# CutMonitor_MCU.net
KiCad netlist of a schematic drawn in Altium Designer
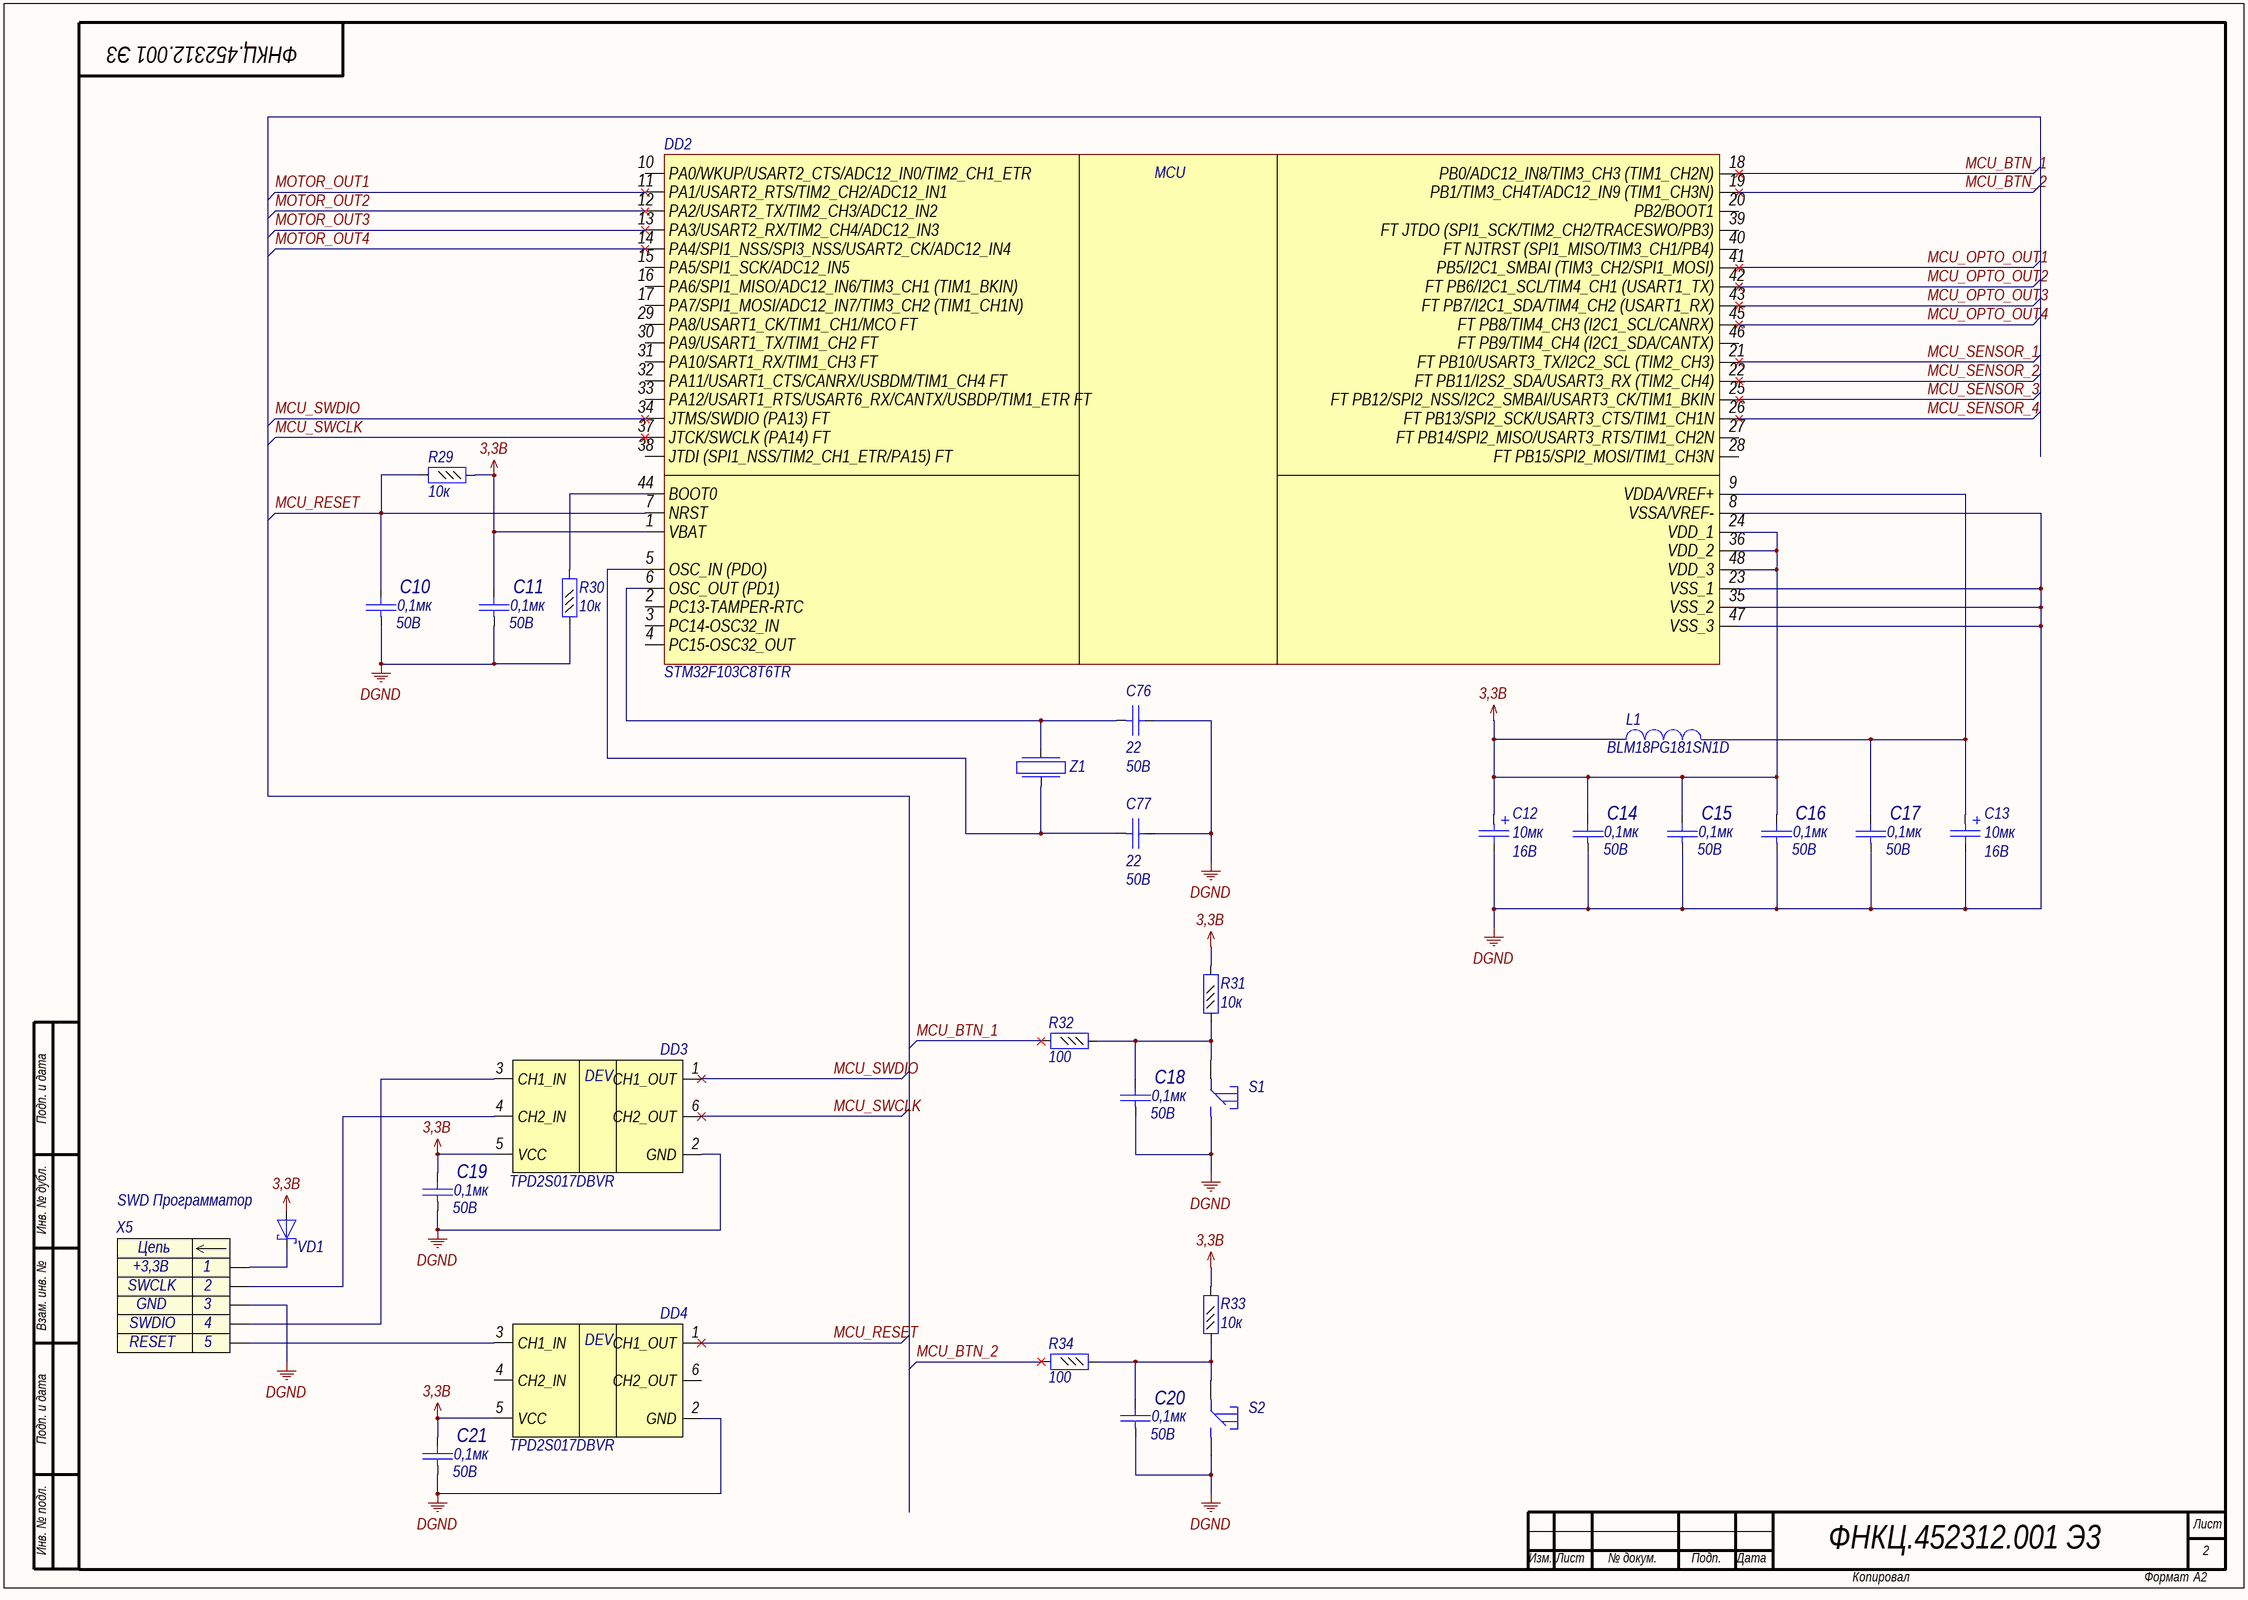
[diagram p0: CutMonitor_MCU.SchDoc]

(export (version "E")
  (design (tool "Eeschema 10.0.6"))
  (components
    (comp (ref "C10")
      (value "0,1мк")
      (footprint "C0603")
      (description "Конденсатор")
      (fields
        (field (name "VOLTAGE") "50B")
        (field (name "PART NUMBER") "GRM188R71H104KA93D")
        (field (name "Comment") "Capacitor")
      )
      (libsource (lib "MOP44") (part "Capacitor"))
    )
    (comp (ref "C11")
      (value "0,1мк")
      (footprint "C0603")
      (description "Конденсатор")
      (fields
        (field (name "VOLTAGE") "50B")
        (field (name "PART NUMBER") "GRM188R71H104KA93D")
        (field (name "Comment") "Capacitor")
      )
      (libsource (lib "MOP44") (part "Capacitor"))
    )
    (comp (ref "C12")
      (value "10мк")
      (footprint "TANTAL CASE A")
      (description "Конденсатор полярный")
      (fields
        (field (name "VOLTAGE") "16В")
        (field (name "PART NUMBER") "293D106X9016A2TE3")
        (field (name "Comment") "Capacitor_pol")
      )
      (libsource (lib "MOP44") (part "Capacitor_pol"))
    )
    (comp (ref "C13")
      (value "10мк")
      (footprint "TANTAL CASE A")
      (description "Конденсатор полярный")
      (fields
        (field (name "VOLTAGE") "16В")
        (field (name "PART NUMBER") "293D106X9016A2TE3")
        (field (name "Comment") "Capacitor_pol")
      )
      (libsource (lib "MOP44") (part "Capacitor_pol"))
    )
    (comp (ref "C14")
      (value "0,1мк")
      (footprint "C0603")
      (description "Конденсатор")
      (fields
        (field (name "VOLTAGE") "50B")
        (field (name "PART NUMBER") "GRM188R71H104KA93D")
        (field (name "Comment") "Capacitor")
      )
      (libsource (lib "MOP44") (part "Capacitor"))
    )
    (comp (ref "C15")
      (value "0,1мк")
      (footprint "C0603")
      (description "Конденсатор")
      (fields
        (field (name "VOLTAGE") "50B")
        (field (name "PART NUMBER") "GRM188R71H104KA93D")
        (field (name "Comment") "Capacitor")
      )
      (libsource (lib "MOP44") (part "Capacitor"))
    )
    (comp (ref "C16")
      (value "0,1мк")
      (footprint "C0603")
      (description "Конденсатор")
      (fields
        (field (name "VOLTAGE") "50B")
        (field (name "PART NUMBER") "GRM188R71H104KA93D")
        (field (name "Comment") "Capacitor")
      )
      (libsource (lib "MOP44") (part "Capacitor"))
    )
    (comp (ref "C17")
      (value "0,1мк")
      (footprint "C0603")
      (description "Конденсатор")
      (fields
        (field (name "VOLTAGE") "50B")
        (field (name "PART NUMBER") "GRM188R71H104KA93D")
        (field (name "Comment") "Capacitor")
      )
      (libsource (lib "MOP44") (part "Capacitor"))
    )
    (comp (ref "C18")
      (value "0,1мк")
      (footprint "C0603")
      (description "Конденсатор")
      (fields
        (field (name "VOLTAGE") "50B")
        (field (name "PART NUMBER") "GRM188R71H104KA93D")
        (field (name "Comment") "Capacitor")
      )
      (libsource (lib "MOP44") (part "Capacitor"))
    )
    (comp (ref "C19")
      (value "0,1мк")
      (footprint "C0603")
      (description "Конденсатор")
      (fields
        (field (name "VOLTAGE") "50B")
        (field (name "PART NUMBER") "GRM188R71H104KA93D")
        (field (name "Comment") "Capacitor")
      )
      (libsource (lib "MOP44") (part "Capacitor"))
    )
    (comp (ref "C20")
      (value "0,1мк")
      (footprint "C0603")
      (description "Конденсатор")
      (fields
        (field (name "VOLTAGE") "50B")
        (field (name "PART NUMBER") "GRM188R71H104KA93D")
        (field (name "Comment") "Capacitor")
      )
      (libsource (lib "MOP44") (part "Capacitor"))
    )
    (comp (ref "C21")
      (value "0,1мк")
      (footprint "C0603")
      (description "Конденсатор")
      (fields
        (field (name "VOLTAGE") "50B")
        (field (name "PART NUMBER") "GRM188R71H104KA93D")
        (field (name "Comment") "Capacitor")
      )
      (libsource (lib "MOP44") (part "Capacitor"))
    )
    (comp (ref "C76")
      (value "22")
      (footprint "C0603")
      (description "Конденсатор")
      (fields
        (field (name "VOLTAGE") "50B")
        (field (name "PART NUMBER") "CC0603JRNPO9BN220")
        (field (name "Comment") "Capacitor")
      )
      (libsource (lib "MOP44") (part "Capacitor"))
    )
    (comp (ref "C77")
      (value "22")
      (footprint "C0603")
      (description "Конденсатор")
      (fields
        (field (name "VOLTAGE") "50B")
        (field (name "PART NUMBER") "CC0603JRNPO9BN220")
        (field (name "Comment") "Capacitor")
      )
      (libsource (lib "MOP44") (part "Capacitor"))
    )
    (comp (ref "DD2")
      (value "STM32F103C8T6TR")
      (footprint "LQFP48")
      (libsource (lib "MOP44") (part "STM32F103C8T6TR"))
    )
    (comp (ref "DD3")
      (value "TPD2S017")
      (footprint "SOT23-6")
      (description "EMI Filter")
      (fields (field (name "PART NUMBER") "TPD2S017DBVR"))
      (libsource (lib "MOP44") (part "TPD2S017"))
    )
    (comp (ref "DD4")
      (value "TPD2S017")
      (footprint "SOT23-6")
      (description "EMI Filter")
      (fields (field (name "PART NUMBER") "TPD2S017DBVR"))
      (libsource (lib "MOP44") (part "TPD2S017"))
    )
    (comp (ref "L1")
      (value "Inductor")
      (footprint "L0603")
      (description "EMI Suppression Filter")
      (fields (field (name "PART NUMBER") "BLM18PG181SN1D"))
      (libsource (lib "MOP44") (part "Inductor"))
    )
    (comp (ref "R29")
      (value "10к")
      (footprint "R0603")
      (description "Резистор")
      (fields (field (name "PART NUMBER") "RC0603FR-0710KL") (field (name "POWER") "0,062Вт"))
      (libsource (lib "") (part "Resistor_0,062Вт_1"))
    )
    (comp (ref "R30")
      (value "10к")
      (footprint "R0603")
      (description "Резистор")
      (fields (field (name "PART NUMBER") "RC0603FR-0710KL") (field (name "POWER") "0,062Вт"))
      (libsource (lib "MOP44") (part "Resistor_0,062Вт"))
    )
    (comp (ref "R31")
      (value "10к")
      (footprint "R0603")
      (description "Резистор")
      (fields (field (name "PART NUMBER") "RC0603FR-0710KL") (field (name "POWER") "0,062Вт"))
      (libsource (lib "MOP44") (part "Resistor_0,062Вт"))
    )
    (comp (ref "R32")
      (value "100")
      (footprint "R0603")
      (description "Резистор")
      (fields (field (name "PART NUMBER") "RC0603FR-07100RL") (field (name "POWER") "0,062Вт"))
      (libsource (lib "") (part "Resistor_0,062Вт_1"))
    )
    (comp (ref "R33")
      (value "10к")
      (footprint "R0603")
      (description "Резистор")
      (fields (field (name "PART NUMBER") "RC0603FR-0710KL") (field (name "POWER") "0,062Вт"))
      (libsource (lib "MOP44") (part "Resistor_0,062Вт"))
    )
    (comp (ref "R34")
      (value "100")
      (footprint "R0603")
      (description "Резистор")
      (fields (field (name "PART NUMBER") "RC0603FR-07100RL") (field (name "POWER") "0,062Вт"))
      (libsource (lib "") (part "Resistor_0,062Вт_1"))
    )
    (comp (ref "S1")
      (value "Button")
      (footprint "Button_SMD")
      (description "Кнопка")
      (libsource (lib "MOP44") (part "Button"))
    )
    (comp (ref "S2")
      (value "Button")
      (footprint "Button_SMD")
      (description "Кнопка")
      (libsource (lib "MOP44") (part "Button"))
    )
    (comp (ref "VD1")
      (value "DiodeSchottky")
      (footprint "SOD-523")
      (description "Диод Шоттки")
      (fields (field (name "PART NUMBER") "PMEG2010AEB.115"))
      (libsource (lib "MOP44") (part "DiodeSchottky"))
    )
    (comp (ref "X5")
      (value "SWD Программатор")
      (footprint "PLS-5")
      (description "Разъем - 5 конт. вилка")
      (fields (field (name "PART NUMBER") "DS1021-1*5SF112-B"))
      (libsource (lib "MOP44") (part "Header_5_plg"))
    )
    (comp (ref "Z1")
      (value "Crystal")
      (footprint "QSMD5.0x3.2x1.0")
      (description "Кварцевый резонатор")
      (fields (field (name "PART NUMBER") "KX-9A"))
      (libsource (lib "MOP44") (part "Crystal"))
    )
  )
  (nets
    (net (code "1") (name "/MCU_BTN_1") (class "Default")
      (node (ref "DD2") (pin "18") (pinfunction "PB0/ADC12_IN8/TIM3_CH3_(TIM1_CH2N)_18") (pintype "passive"))
      (node (ref "R32") (pin "2") (pinfunction "2_2") (pintype "passive"))
    )
    (net (code "2") (name "/MCU_BTN_2") (class "Default")
      (node (ref "DD2") (pin "19") (pinfunction "PB1/TIM3_CH4T/ADC12_IN9_(TIM1_CH3N)_19") (pintype "passive"))
      (node (ref "R34") (pin "2") (pinfunction "2_2") (pintype "passive"))
    )
    (net (code "3") (name "/MCU_OPTO_OUT1") (class "Default")
      (node (ref "DD2") (pin "41") (pinfunction "PB5/I2C1_SMBAI_(TIM3_CH2/SPI1_MOSI)_41") (pintype "passive+no_connect"))
    )
    (net (code "4") (name "/MCU_OPTO_OUT2") (class "Default")
      (node (ref "DD2") (pin "42") (pinfunction "FT_PB6/I2C1_SCL/TIM4_CH1_(USART1_TX)_42") (pintype "passive+no_connect"))
    )
    (net (code "5") (name "/MCU_OPTO_OUT3") (class "Default")
      (node (ref "DD2") (pin "43") (pinfunction "FT_PB7/I2C1_SDA/TIM4_CH2_(USART1_RX)_43") (pintype "passive+no_connect"))
    )
    (net (code "6") (name "/MCU_OPTO_OUT4") (class "Default")
      (node (ref "DD2") (pin "45") (pinfunction "FT_PB8/TIM4_CH3_(I2C1_SCL/CANRX)_45") (pintype "passive+no_connect"))
    )
    (net (code "7") (name "/MCU_RESET") (class "Default")
      (node (ref "C10") (pin "2") (pinfunction "2_2") (pintype "passive"))
      (node (ref "DD2") (pin "7") (pinfunction "NRST_7") (pintype "passive"))
      (node (ref "DD4") (pin "1") (pinfunction "CH1_OUT_1") (pintype "passive"))
      (node (ref "R29") (pin "2") (pinfunction "2_2") (pintype "passive"))
    )
    (net (code "8") (name "/MCU_SENSOR_1") (class "Default")
      (node (ref "DD2") (pin "21") (pinfunction "FT_PB10/USART3_TX/I2C2_SCL_(TIM2_CH3)_21") (pintype "passive+no_connect"))
    )
    (net (code "9") (name "/MCU_SENSOR_2") (class "Default")
      (node (ref "DD2") (pin "22") (pinfunction "FT_PB11/I2S2_SDA/USART3_RX_(TIM2_CH4)_22") (pintype "passive+no_connect"))
    )
    (net (code "10") (name "/MCU_SENSOR_3") (class "Default")
      (node (ref "DD2") (pin "25") (pinfunction "FT_PB12/SPI2_NSS/I2C2_SMBAI/USART3_CK/TIM1_BKIN_25") (pintype "passive+no_connect"))
    )
    (net (code "11") (name "/MCU_SENSOR_4") (class "Default")
      (node (ref "DD2") (pin "26") (pinfunction "FT_PB13/SPI2_SCK/USART3_CTS/TIM1_CH1N_26") (pintype "passive+no_connect"))
    )
    (net (code "12") (name "/MCU_SWCLK") (class "Default")
      (node (ref "DD2") (pin "37") (pinfunction "JTCK/SWCLK_(PA14)_FT_37") (pintype "passive"))
      (node (ref "DD3") (pin "6") (pinfunction "CH2_OUT_6") (pintype "passive"))
    )
    (net (code "13") (name "/MCU_SWDIO") (class "Default")
      (node (ref "DD2") (pin "34") (pinfunction "JTMS/SWDIO_(PA13)_FT_34") (pintype "passive"))
      (node (ref "DD3") (pin "1") (pinfunction "CH1_OUT_1") (pintype "passive"))
    )
    (net (code "14") (name "/MOTOR_OUT1") (class "Default")
      (node (ref "DD2") (pin "11") (pinfunction "PA1/USART2_RTS/TIM2_CH2/ADC12_IN1_11") (pintype "passive+no_connect"))
    )
    (net (code "15") (name "/MOTOR_OUT2") (class "Default")
      (node (ref "DD2") (pin "12") (pinfunction "PA2/USART2_TX/TIM2_CH3/ADC12_IN2_12") (pintype "passive+no_connect"))
    )
    (net (code "16") (name "/MOTOR_OUT3") (class "Default")
      (node (ref "DD2") (pin "13") (pinfunction "PA3/USART2_RX/TIM2_CH4/ADC12_IN3_13") (pintype "passive+no_connect"))
    )
    (net (code "17") (name "/MOTOR_OUT4") (class "Default")
      (node (ref "DD2") (pin "14") (pinfunction "PA4/SPI1_NSS/SPI3_NSS/USART2_CK/ADC12_IN4_14") (pintype "passive+no_connect"))
    )
    (net (code "18") (name "3,3B") (class "Default")
      (node (ref "C11") (pin "2") (pinfunction "2_2") (pintype "passive"))
      (node (ref "C12") (pin "1") (pinfunction "1_1") (pintype "passive"))
      (node (ref "C14") (pin "2") (pinfunction "2_2") (pintype "passive"))
      (node (ref "C15") (pin "2") (pinfunction "2_2") (pintype "passive"))
      (node (ref "C16") (pin "2") (pinfunction "2_2") (pintype "passive"))
      (node (ref "C19") (pin "2") (pinfunction "2_2") (pintype "passive"))
      (node (ref "C21") (pin "2") (pinfunction "2_2") (pintype "passive"))
      (node (ref "DD2") (pin "1") (pinfunction "VBAT_1") (pintype "passive"))
      (node (ref "DD2") (pin "24") (pinfunction "VDD_1_24") (pintype "passive"))
      (node (ref "DD2") (pin "36") (pinfunction "VDD_2_36") (pintype "passive"))
      (node (ref "DD2") (pin "48") (pinfunction "VDD_3_48") (pintype "passive"))
      (node (ref "DD3") (pin "5") (pinfunction "VCC_5") (pintype "power_in"))
      (node (ref "DD4") (pin "5") (pinfunction "VCC_5") (pintype "power_in"))
      (node (ref "L1") (pin "1") (pinfunction "1_1") (pintype "passive"))
      (node (ref "R29") (pin "1") (pinfunction "1_1") (pintype "passive"))
      (node (ref "R31") (pin "2") (pinfunction "2_2") (pintype "passive"))
      (node (ref "R33") (pin "2") (pinfunction "2_2") (pintype "passive"))
      (node (ref "VD1") (pin "2") (pinfunction "A_2") (pintype "passive"))
    )
    (net (code "19") (name "DGND") (class "Default")
      (node (ref "C10") (pin "1") (pinfunction "1_1") (pintype "passive"))
      (node (ref "C11") (pin "1") (pinfunction "1_1") (pintype "passive"))
      (node (ref "C12") (pin "2") (pinfunction "2_2") (pintype "passive"))
      (node (ref "C13") (pin "2") (pinfunction "2_2") (pintype "passive"))
      (node (ref "C14") (pin "1") (pinfunction "1_1") (pintype "passive"))
      (node (ref "C15") (pin "1") (pinfunction "1_1") (pintype "passive"))
      (node (ref "C16") (pin "1") (pinfunction "1_1") (pintype "passive"))
      (node (ref "C17") (pin "1") (pinfunction "1_1") (pintype "passive"))
      (node (ref "C18") (pin "1") (pinfunction "1_1") (pintype "passive"))
      (node (ref "C19") (pin "1") (pinfunction "1_1") (pintype "passive"))
      (node (ref "C20") (pin "1") (pinfunction "1_1") (pintype "passive"))
      (node (ref "C21") (pin "1") (pinfunction "1_1") (pintype "passive"))
      (node (ref "C76") (pin "2") (pinfunction "2_2") (pintype "passive"))
      (node (ref "C77") (pin "2") (pinfunction "2_2") (pintype "passive"))
      (node (ref "DD2") (pin "23") (pinfunction "VSS_1_23") (pintype "passive"))
      (node (ref "DD2") (pin "35") (pinfunction "VSS_2_35") (pintype "passive"))
      (node (ref "DD2") (pin "47") (pinfunction "VSS_3_47") (pintype "passive"))
      (node (ref "DD2") (pin "8") (pinfunction "VSSA/VREF-_8") (pintype "passive"))
      (node (ref "DD3") (pin "2") (pinfunction "GND_2") (pintype "power_in"))
      (node (ref "DD4") (pin "2") (pinfunction "GND_2") (pintype "power_in"))
      (node (ref "R30") (pin "1") (pinfunction "1_1") (pintype "passive"))
      (node (ref "S1") (pin "4") (pinfunction "4_4") (pintype "passive"))
      (node (ref "S2") (pin "4") (pinfunction "4_4") (pintype "passive"))
      (node (ref "X5") (pin "3") (pinfunction "3_3") (pintype "passive"))
    )
    (net (code "20") (name "Net-(C18-Pad2)") (class "Default")
      (node (ref "C18") (pin "2") (pinfunction "2_2") (pintype "passive"))
      (node (ref "R31") (pin "1") (pinfunction "1_1") (pintype "passive"))
      (node (ref "R32") (pin "1") (pinfunction "1_1") (pintype "passive"))
      (node (ref "S1") (pin "1") (pinfunction "1_1") (pintype "passive"))
    )
    (net (code "21") (name "Net-(C20-Pad2)") (class "Default")
      (node (ref "C20") (pin "2") (pinfunction "2_2") (pintype "passive"))
      (node (ref "R33") (pin "1") (pinfunction "1_1") (pintype "passive"))
      (node (ref "R34") (pin "1") (pinfunction "1_1") (pintype "passive"))
      (node (ref "S2") (pin "1") (pinfunction "1_1") (pintype "passive"))
    )
    (net (code "22") (name "Net-(DD2-BOOT0)") (class "Default")
      (node (ref "DD2") (pin "44") (pinfunction "BOOT0_44") (pintype "passive"))
      (node (ref "R30") (pin "2") (pinfunction "2_2") (pintype "passive"))
    )
    (net (code "23") (name "Net-(DD2-OSC_IN_(PDO))") (class "Default")
      (node (ref "C77") (pin "1") (pinfunction "1_1") (pintype "passive"))
      (node (ref "DD2") (pin "5") (pinfunction "OSC_IN_(PDO)_5") (pintype "passive"))
      (node (ref "Z1") (pin "1") (pinfunction "1_1") (pintype "passive"))
    )
    (net (code "24") (name "Net-(DD2-OSC_OUT_(PD1))") (class "Default")
      (node (ref "C76") (pin "1") (pinfunction "1_1") (pintype "passive"))
      (node (ref "DD2") (pin "6") (pinfunction "OSC_OUT_(PD1)_6") (pintype "passive"))
      (node (ref "Z1") (pin "2") (pinfunction "2_2") (pintype "passive"))
    )
    (net (code "25") (name "Net-(DD2-VDDA{slash}VREF+)") (class "Default")
      (node (ref "C13") (pin "1") (pinfunction "1_1") (pintype "passive"))
      (node (ref "C17") (pin "2") (pinfunction "2_2") (pintype "passive"))
      (node (ref "DD2") (pin "9") (pinfunction "VDDA/VREF+_9") (pintype "passive"))
      (node (ref "L1") (pin "2") (pinfunction "2_2") (pintype "passive"))
    )
    (net (code "26") (name "Net-(DD3-CH1_IN)") (class "Default")
      (node (ref "DD3") (pin "3") (pinfunction "CH1_IN_3") (pintype "passive"))
      (node (ref "X5") (pin "4") (pinfunction "4_4") (pintype "passive"))
    )
    (net (code "27") (name "Net-(DD3-CH2_IN)") (class "Default")
      (node (ref "DD3") (pin "4") (pinfunction "CH2_IN_4") (pintype "passive"))
      (node (ref "X5") (pin "2") (pinfunction "2_2") (pintype "passive"))
    )
    (net (code "28") (name "Net-(DD4-CH1_IN)") (class "Default")
      (node (ref "DD4") (pin "3") (pinfunction "CH1_IN_3") (pintype "passive"))
      (node (ref "X5") (pin "5") (pinfunction "5_5") (pintype "passive"))
    )
    (net (code "29") (name "Net-(VD1-K)") (class "Default")
      (node (ref "VD1") (pin "1") (pinfunction "K_1") (pintype "passive"))
      (node (ref "X5") (pin "1") (pinfunction "1_1") (pintype "passive"))
    )
    (net (code "30") (name "unconnected-(DD2-FT_JTDO_(SPI1_SCK{slash}TIM2_CH2{slash}TRACESWO{slash}PB3)-Pad39)") (class "Default")
      (node (ref "DD2") (pin "39") (pinfunction "FT_JTDO_(SPI1_SCK/TIM2_CH2/TRACESWO/PB3)_39") (pintype "passive"))
    )
    (net (code "31") (name "unconnected-(DD2-FT_NJTRST_(SPI1_MISO{slash}TIM3_CH1{slash}PB4)-Pad40)") (class "Default")
      (node (ref "DD2") (pin "40") (pinfunction "FT_NJTRST_(SPI1_MISO/TIM3_CH1/PB4)_40") (pintype "passive"))
    )
    (net (code "32") (name "unconnected-(DD2-FT_PB9{slash}TIM4_CH4_(I2C1_SDA{slash}CANTX)-Pad46)") (class "Default")
      (node (ref "DD2") (pin "46") (pinfunction "FT_PB9/TIM4_CH4_(I2C1_SDA/CANTX)_46") (pintype "passive"))
    )
    (net (code "33") (name "unconnected-(DD2-FT_PB14{slash}SPI2_MISO{slash}USART3_RTS{slash}TIM1_CH2N-Pad27)") (class "Default")
      (node (ref "DD2") (pin "27") (pinfunction "FT_PB14/SPI2_MISO/USART3_RTS/TIM1_CH2N_27") (pintype "passive"))
    )
    (net (code "34") (name "unconnected-(DD2-FT_PB15{slash}SPI2_MOSI{slash}TIM1_CH3N-Pad28)") (class "Default")
      (node (ref "DD2") (pin "28") (pinfunction "FT_PB15/SPI2_MOSI/TIM1_CH3N_28") (pintype "passive"))
    )
    (net (code "35") (name "unconnected-(DD2-JTDI_(SPI1_NSS{slash}TIM2_CH1_ETR{slash}PA15)_FT-Pad38)") (class "Default")
      (node (ref "DD2") (pin "38") (pinfunction "JTDI_(SPI1_NSS/TIM2_CH1_ETR/PA15)_FT_38") (pintype "passive"))
    )
    (net (code "36") (name "unconnected-(DD2-PA0{slash}WKUP{slash}USART2_CTS{slash}ADC12_IN0{slash}TIM2_CH1_ETR-Pad10)") (class "Default")
      (node (ref "DD2") (pin "10") (pinfunction "PA0/WKUP/USART2_CTS/ADC12_IN0/TIM2_CH1_ETR_10") (pintype "passive"))
    )
    (net (code "37") (name "unconnected-(DD2-PA5{slash}SPI1_SCK{slash}ADC12_IN5-Pad15)") (class "Default")
      (node (ref "DD2") (pin "15") (pinfunction "PA5/SPI1_SCK/ADC12_IN5_15") (pintype "passive"))
    )
    (net (code "38") (name "unconnected-(DD2-PA6{slash}SPI1_MISO{slash}ADC12_IN6{slash}TIM3_CH1_(TIM1_BKIN)-Pad16)") (class "Default")
      (node (ref "DD2") (pin "16") (pinfunction "PA6/SPI1_MISO/ADC12_IN6/TIM3_CH1_(TIM1_BKIN)_16") (pintype "passive"))
    )
    (net (code "39") (name "unconnected-(DD2-PA7{slash}SPI1_MOSI{slash}ADC12_IN7{slash}TIM3_CH2_(TIM1_CH1N)-Pad17)") (class "Default")
      (node (ref "DD2") (pin "17") (pinfunction "PA7/SPI1_MOSI/ADC12_IN7/TIM3_CH2_(TIM1_CH1N)_17") (pintype "passive"))
    )
    (net (code "40") (name "unconnected-(DD2-PA8{slash}USART1_CK{slash}TIM1_CH1{slash}MCO_FT-Pad29)") (class "Default")
      (node (ref "DD2") (pin "29") (pinfunction "PA8/USART1_CK/TIM1_CH1/MCO_FT_29") (pintype "passive"))
    )
    (net (code "41") (name "unconnected-(DD2-PA9{slash}USART1_TX{slash}TIM1_CH2_FT-Pad30)") (class "Default")
      (node (ref "DD2") (pin "30") (pinfunction "PA9/USART1_TX/TIM1_CH2_FT_30") (pintype "passive"))
    )
    (net (code "42") (name "unconnected-(DD2-PA10{slash}SART1_RX{slash}TIM1_CH3_FT-Pad31)") (class "Default")
      (node (ref "DD2") (pin "31") (pinfunction "PA10/SART1_RX/TIM1_CH3_FT_31") (pintype "passive"))
    )
    (net (code "43") (name "unconnected-(DD2-PA11{slash}USART1_CTS{slash}CANRX{slash}USBDM{slash}TIM1_CH4_FT-Pad32)") (class "Default")
      (node (ref "DD2") (pin "32") (pinfunction "PA11/USART1_CTS/CANRX/USBDM/TIM1_CH4_FT_32") (pintype "passive"))
    )
    (net (code "44") (name "unconnected-(DD2-PA12{slash}USART1_RTS{slash}USART6_RX{slash}CANTX{slash}USBDP{slash}TIM1_ETR_FT-Pad33)") (class "Default")
      (node (ref "DD2") (pin "33") (pinfunction "PA12/USART1_RTS/USART6_RX/CANTX/USBDP/TIM1_ETR_FT_33") (pintype "passive"))
    )
    (net (code "45") (name "unconnected-(DD2-PB2{slash}BOOT1-Pad20)") (class "Default")
      (node (ref "DD2") (pin "20") (pinfunction "PB2/BOOT1_20") (pintype "passive"))
    )
    (net (code "46") (name "unconnected-(DD2-PC13-TAMPER-RTC-Pad2)") (class "Default")
      (node (ref "DD2") (pin "2") (pinfunction "PC13-TAMPER-RTC_2") (pintype "passive"))
    )
    (net (code "47") (name "unconnected-(DD2-PC14-OSC32_IN-Pad3)") (class "Default")
      (node (ref "DD2") (pin "3") (pinfunction "PC14-OSC32_IN_3") (pintype "passive"))
    )
    (net (code "48") (name "unconnected-(DD2-PC15-OSC32_OUT-Pad4)") (class "Default")
      (node (ref "DD2") (pin "4") (pinfunction "PC15-OSC32_OUT_4") (pintype "passive"))
    )
    (net (code "49") (name "unconnected-(DD4-CH2_IN-Pad4)") (class "Default")
      (node (ref "DD4") (pin "4") (pinfunction "CH2_IN_4") (pintype "passive"))
    )
    (net (code "50") (name "unconnected-(DD4-CH2_OUT-Pad6)") (class "Default")
      (node (ref "DD4") (pin "6") (pinfunction "CH2_OUT_6") (pintype "passive"))
    )
  )
)
